# ESP_PIC_V2.net
KiCad netlist of a schematic drawn in Altium Designer
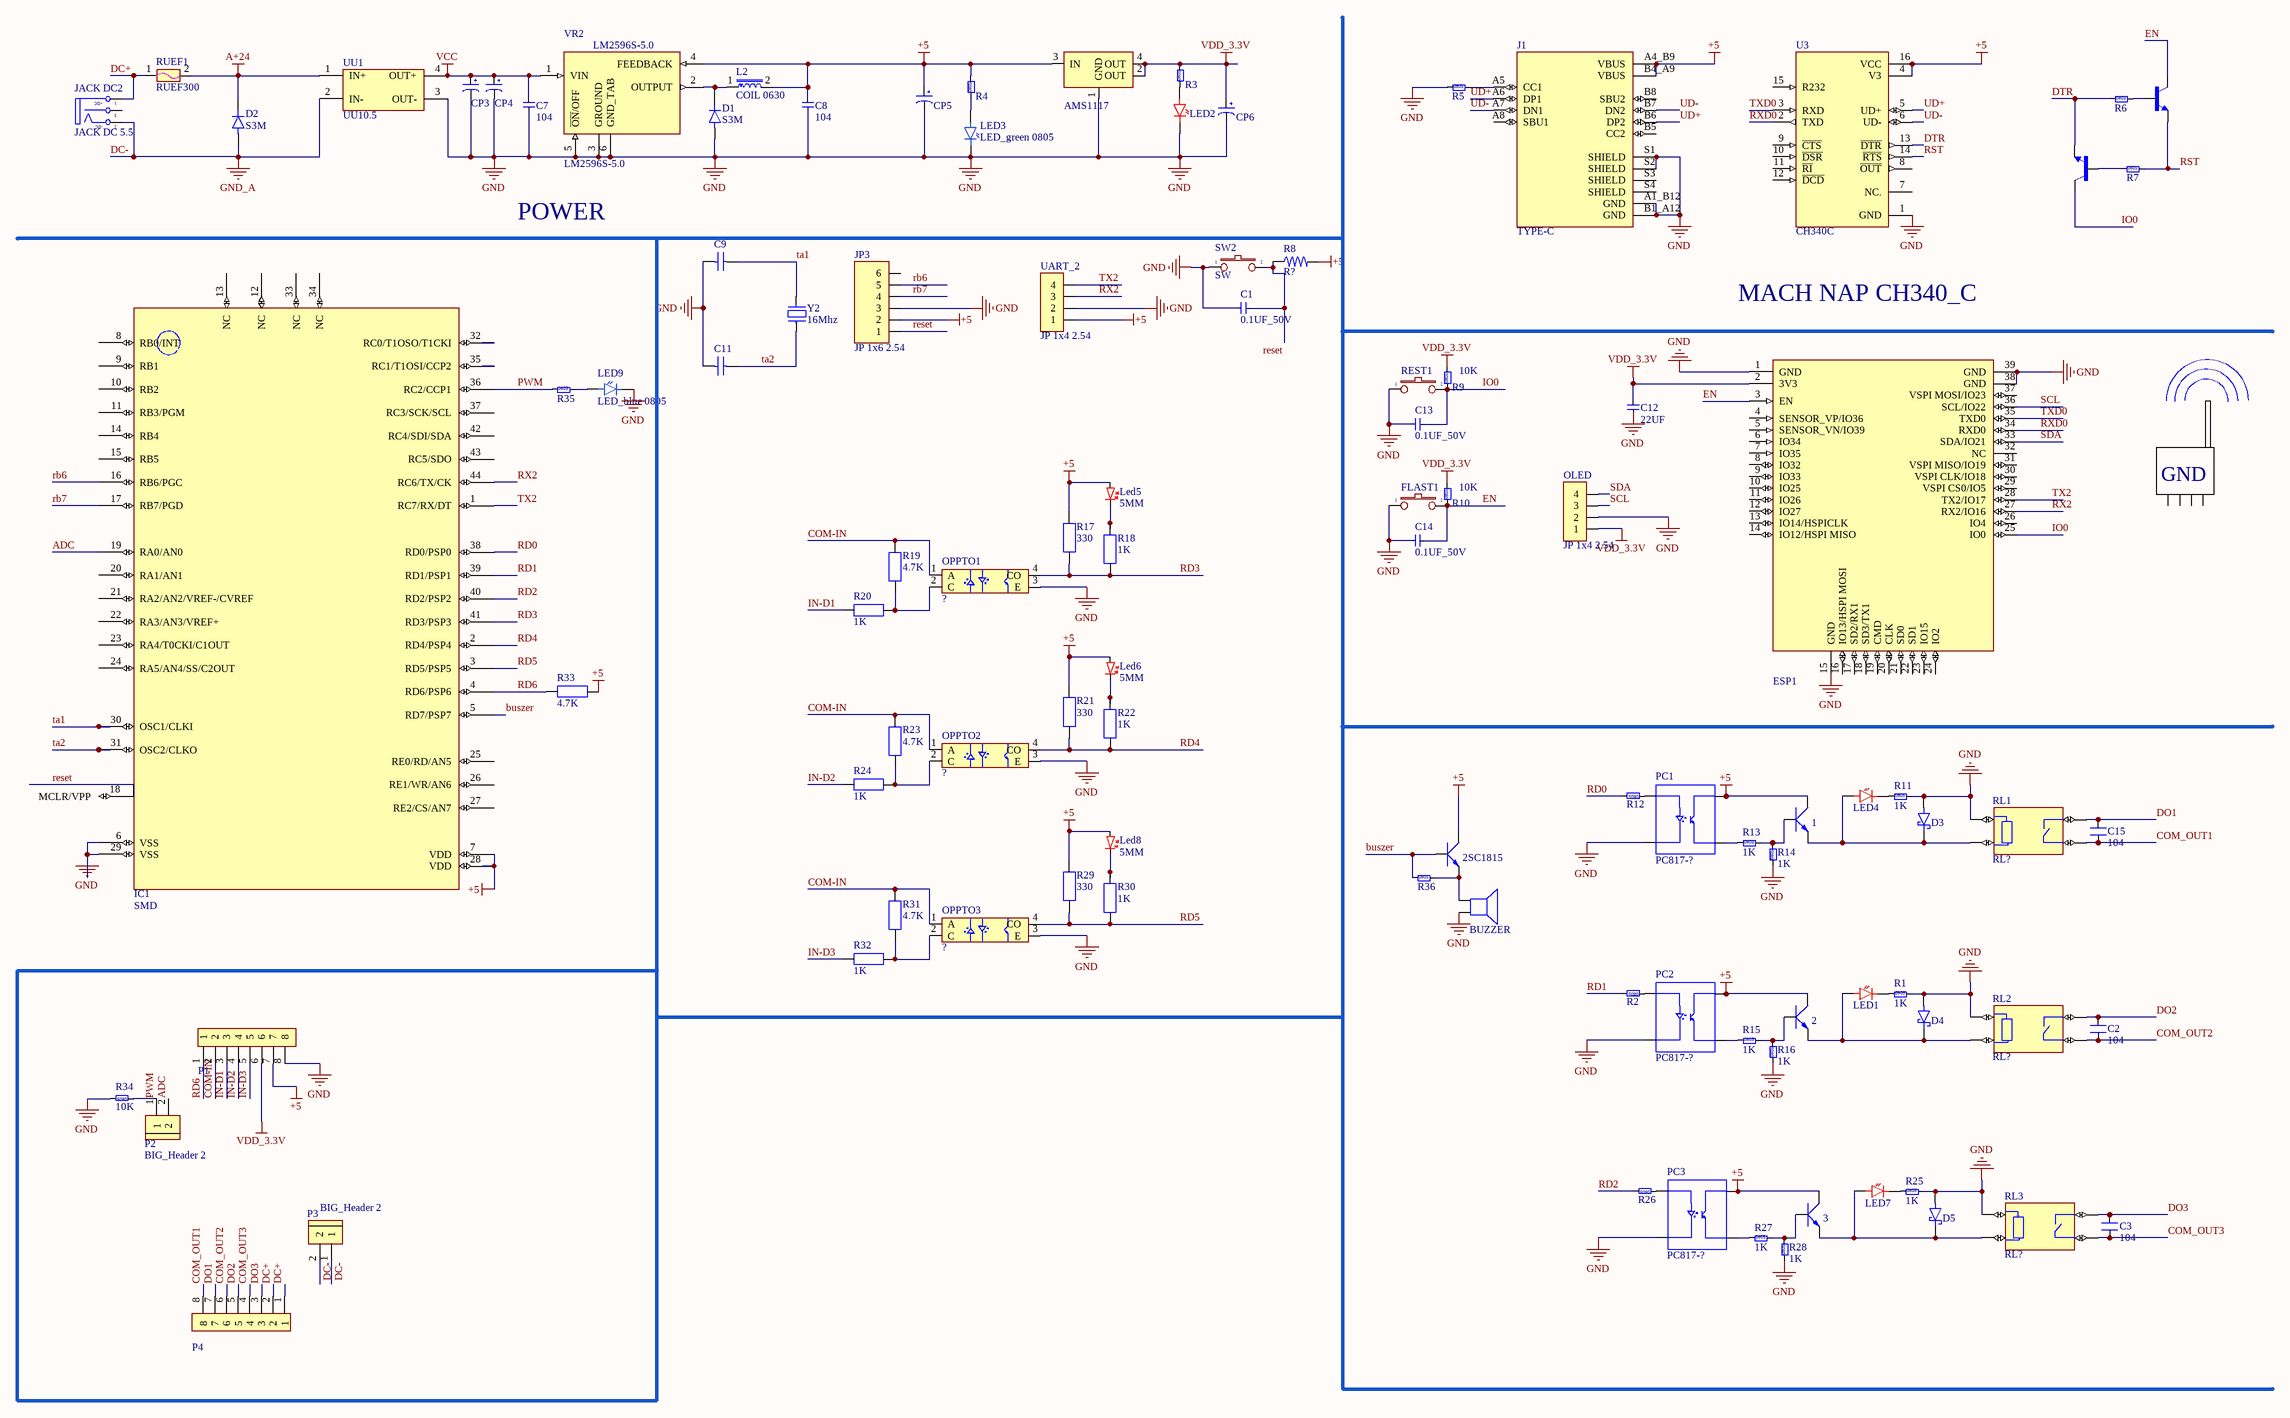
[diagram p0: ESP_PIC_V2.SchDoc]

(export (version "E")
  (design (tool "Eeschema 10.0.6"))
  (components
    (comp (ref "1")
      (value "2SC1815")
      (footprint "SOT23-3")
      (description "NPN-0.15A-50V")
      (libsource (lib "PLG_RC") (part "2SC1815-SMD"))
    )
    (comp (ref "2")
      (value "2SC1815")
      (footprint "SOT23-3")
      (description "NPN-0.15A-50V")
      (libsource (lib "PLG_RC") (part "2SC1815-SMD"))
    )
    (comp (ref "2SC1815")
      (value "2SC1815")
      (footprint "SOT23-3")
      (description "NPN-0.15A-50V")
      (libsource (lib "PLG_RC") (part "2SC1815-SMD"))
    )
    (comp (ref "3")
      (value "2SC1815")
      (footprint "SOT23-3")
      (description "NPN-0.15A-50V")
      (libsource (lib "PLG_RC") (part "2SC1815-SMD"))
    )
    (comp (ref "AMS1117")
      (value "AMS1117")
      (footprint "SOT223-4M_AMS1117_3V3")
      (description "800mA- 3.3V - SMD")
      (libsource (lib "PLG_RC") (part "AMS1117-3.3-SMD"))
    )
    (comp (ref "BUZZER")
      (value "BUZZER")
      (footprint "Coi Chip Speacker")
      (description "Còi chip")
      (libsource (lib "PLG_RC") (part "BUZZER"))
    )
    (comp (ref "C1")
      (value "0.1UF_50V")
      (footprint "CAP0805")
      (description "CAP 0805 KHÔNG PHÂN CỰC SMD")
      (fields
        (field (name "MANUFACTURER") "TDK Corporation")
        (field (name "MANUFACTURER PART NUMBER") "C3216JB1V226M160AC")
      )
      (libsource (lib "PLG_RC") (part "CAP 0805"))
    )
    (comp (ref "C2")
      (value "104")
      (footprint "CN2")
      (description "Cap np 104 => 105pF")
      (libsource (lib "TH_PHUOC") (part "CN2"))
    )
    (comp (ref "C3")
      (value "104")
      (footprint "CN2")
      (description "Cap np 104 => 105pF")
      (libsource (lib "TH_PHUOC") (part "CN2"))
    )
    (comp (ref "C7")
      (value "104")
      (footprint "CAP0805")
      (description "CAP 0805 KHÔNG PHÂN CỰC SMD")
      (fields
        (field (name "MANUFACTURER") "TDK Corporation")
        (field (name "MANUFACTURER PART NUMBER") "C3216JB1V226M160AC")
      )
      (libsource (lib "PLG_RC") (part "CAP 0805"))
    )
    (comp (ref "C8")
      (value "104")
      (footprint "CAP0805")
      (description "CAP 0805 KHÔNG PHÂN CỰC SMD")
      (fields
        (field (name "MANUFACTURER") "TDK Corporation")
        (field (name "MANUFACTURER PART NUMBER") "C3216JB1V226M160AC")
      )
      (libsource (lib "PLG_RC") (part "CAP 0805"))
    )
    (comp (ref "C9")
      (value "Capacitor Ceramic")
      (footprint "C0805")
      (description "Capacitor")
      (fields (field (name "PUBLISHER") "Altium Limited"))
      (libsource (lib "Cty1") (part "CapSMD"))
    )
    (comp (ref "C11")
      (value "Capacitor Ceramic")
      (footprint "C0805")
      (description "Capacitor")
      (fields (field (name "PUBLISHER") "Altium Limited"))
      (libsource (lib "Cty1") (part "CapSMD"))
    )
    (comp (ref "C12")
      (value "22UF")
      (footprint "CAP0805")
      (description "CAP 0805 KHÔNG PHÂN CỰC SMD")
      (fields
        (field (name "MANUFACTURER") "TDK Corporation")
        (field (name "MANUFACTURER PART NUMBER") "C3216JB1V226M160AC")
      )
      (libsource (lib "PLG_RC") (part "CAP 0805"))
    )
    (comp (ref "C13")
      (value "0.1UF_50V")
      (footprint "CAP0805")
      (description "CAP 0805 KHÔNG PHÂN CỰC SMD")
      (fields
        (field (name "MANUFACTURER") "TDK Corporation")
        (field (name "MANUFACTURER PART NUMBER") "C3216JB1V226M160AC")
      )
      (libsource (lib "PLG_RC") (part "CAP 0805"))
    )
    (comp (ref "C14")
      (value "0.1UF_50V")
      (footprint "CAP0805")
      (description "CAP 0805 KHÔNG PHÂN CỰC SMD")
      (fields
        (field (name "MANUFACTURER") "TDK Corporation")
        (field (name "MANUFACTURER PART NUMBER") "C3216JB1V226M160AC")
      )
      (libsource (lib "PLG_RC") (part "CAP 0805"))
    )
    (comp (ref "C15")
      (value "104")
      (footprint "CN2")
      (description "Cap np 104 => 105pF")
      (libsource (lib "TH_PHUOC") (part "CN2"))
    )
    (comp (ref "CP3")
      (value "CP?")
      (footprint "C10mm")
      (description "CP 1000UF/35V")
      (libsource (lib "PLG_RC") (part "CP 1000UF/35V"))
    )
    (comp (ref "CP4")
      (value "CP?")
      (footprint "C10mm")
      (description "CP 1000UF/35V")
      (libsource (lib "PLG_RC") (part "CP 1000UF/35V"))
    )
    (comp (ref "CP5")
      (value "220UF/16V")
      (footprint "CAP SMD ALUMINUM D8")
      (description "SMD")
      (libsource (lib "PLG_RC") (part "TỤ NHÔM 220UF 16V"))
    )
    (comp (ref "CP6")
      (value "220UF/16V")
      (footprint "CAP SMD ALUMINUM D8")
      (description "SMD")
      (libsource (lib "PLG_RC") (part "TỤ NHÔM 220UF 16V"))
    )
    (comp (ref "D1")
      (value "S3M")
      (footprint "S3M")
      (description "Diode Standard 1000 V 3A Surface Mount SMC (DO-214AB)")
      (fields (field (name "MF") "ON Semiconductor"))
      (libsource (lib "PLG_RC") (part "S3M"))
    )
    (comp (ref "D2")
      (value "S3M")
      (footprint "S3M")
      (description "Diode Standard 1000 V 3A Surface Mount SMC (DO-214AB)")
      (fields (field (name "MF") "ON Semiconductor"))
      (libsource (lib "PLG_RC") (part "S3M"))
    )
    (comp (ref "D3")
      (value "D?")
      (footprint "SS210")
      (description "2A, 100V, Schottky Rectifier")
      (fields (field (name "MF") "Taiwan Semiconductor") (field (name "MP") "SS210"))
      (libsource (lib "LeQuangDinh") (part "SS210"))
    )
    (comp (ref "D4")
      (value "D?")
      (footprint "SS210")
      (description "2A, 100V, Schottky Rectifier")
      (fields (field (name "MF") "Taiwan Semiconductor") (field (name "MP") "SS210"))
      (libsource (lib "LeQuangDinh") (part "SS210"))
    )
    (comp (ref "D5")
      (value "D?")
      (footprint "SS210")
      (description "2A, 100V, Schottky Rectifier")
      (fields (field (name "MF") "Taiwan Semiconductor") (field (name "MP") "SS210"))
      (libsource (lib "LeQuangDinh") (part "SS210"))
    )
    (comp (ref "ESP1") (value "ESP32-U") (footprint "ESP32-U") (libsource (lib "PLG_RC") (part "ESP32-U")))
    (comp (ref "FLAST1")
      (value "BUTTON?")
      (footprint "SW1-SMD")
      (description "button 2 pin")
      (libsource (lib "PLG_RC") (part "BUTTON"))
    )
    (comp (ref "IC1")
      (value "SMD")
      (footprint "TQFP_44pin")
      (description "IC SMD")
      (libsource (lib "MIHPHONG_lib") (part "16F877A SMD"))
    )
    (comp (ref "IPEX")
      (value "IPEX")
      (footprint "DE ANTEN ESP")
      (libsource (lib "PLG_RC") (part "ANTEN_IPEX_SMA"))
    )
    (comp (ref "J1")
      (value "TYPE-C")
      (footprint "USB-TYPE-C")
      (description "USB Connectors 24 Receptacle 1 8.94*7.3mm RoHS")
      (fields (field (name "MF") "HRO Electronics Co., Ltd.") (field (name "MP") "TYPE-C-31-M-12"))
      (libsource (lib "PLG_RC") (part "TYPE-C"))
    )
    (comp (ref "JACK DC2")
      (value "JACK DC 5.5")
      (footprint "JACK DC 5.5")
      (libsource (lib "PLG_RC") (part "JACK DC 5.5"))
    )
    (comp (ref "JP3")
      (value "JP 1x6 2.54")
      (footprint "JP 1x6 DT")
      (description "Cắm")
      (libsource (lib "LeQuangDinh1") (part "JP 1x6 2.54 Duc Thang"))
    )
    (comp (ref "L2")
      (value "COIL 0630")
      (footprint "COIL 0630")
      (description "SMD Inductor 10uH-20%-5A")
      (fields (field (name "MP") "CSAB0630-100M") (field (name "MF") "Codaca"))
      (libsource (lib "PLG_RC") (part "COIL 0630"))
    )
    (comp (ref "LED1")
      (value "LED?")
      (footprint "LED_SMD0805_RED - duplicate")
      (description "SMD 0805")
      (libsource (lib "LeQuangDinh") (part "LED SMD 0805"))
    )
    (comp (ref "LED2")
      (value "LED?")
      (footprint "LEDBLUE 0805")
      (description "SMD 0805")
      (libsource (lib "PLG_RC") (part "LED SMD"))
    )
    (comp (ref "LED3")
      (value "LED_green 0805")
      (footprint "LEDgreen 0805")
      (libsource (lib "PLG_RC") (part "LED_green 0805"))
    )
    (comp (ref "LED4")
      (value "LED?")
      (footprint "LED_SMD0805_RED - duplicate")
      (description "SMD 0805")
      (libsource (lib "LeQuangDinh") (part "LED SMD 0805"))
    )
    (comp (ref "Led5")
      (value "5MM")
      (footprint "LEDGREEN 0805")
      (libsource (lib "lequandinh tinker") (part "LED RED 5MM"))
    )
    (comp (ref "Led6")
      (value "5MM")
      (footprint "LEDGREEN 0805")
      (libsource (lib "lequandinh tinker") (part "LED RED 5MM"))
    )
    (comp (ref "LED7")
      (value "LED?")
      (footprint "LED_SMD0805_RED - duplicate")
      (description "SMD 0805")
      (libsource (lib "LeQuangDinh") (part "LED SMD 0805"))
    )
    (comp (ref "Led8")
      (value "5MM")
      (footprint "LEDGREEN 0805")
      (libsource (lib "lequandinh tinker") (part "LED RED 5MM"))
    )
    (comp (ref "LED9")
      (value "LED_blue 0805")
      (footprint "LEDblue 0805")
      (libsource (lib "PLG_RC") (part "LED_blue 0805"))
    )
    (comp (ref "OLED")
      (value "JP 1x4 2.54")
      (footprint "JP 1x4 DT")
      (description "Cắm")
      (libsource (lib "PLG_RC") (part "JP 1x4 2.54 Duc Thang"))
    )
    (comp (ref "OPPTO1")
      (value "?")
      (footprint "OPTO_4-SMD")
      (description "SMD")
      (libsource (lib "lequandinh tinker") (part "OPTO 2C"))
    )
    (comp (ref "OPPTO2")
      (value "?")
      (footprint "OPTO_4-SMD")
      (description "SMD")
      (libsource (lib "lequandinh tinker") (part "OPTO 2C"))
    )
    (comp (ref "OPPTO3")
      (value "?")
      (footprint "OPTO_4-SMD")
      (description "SMD")
      (libsource (lib "lequandinh tinker") (part "OPTO 2C"))
    )
    (comp (ref "P1")
      (value "BIG Heager 8")
      (footprint "BIG_Header 8")
      (libsource (lib "TH_PHUOC") (part "BIG_Header 8"))
    )
    (comp (ref "P2")
      (value "BIG_Header 2")
      (footprint "BIG_Header 2")
      (libsource (lib "") (part "BIG_Header 2_1"))
    )
    (comp (ref "P3")
      (value "BIG_Header 2")
      (footprint "BIG_Header 2")
      (libsource (lib "TH_PHUOC") (part "BIG_Header 2"))
    )
    (comp (ref "P4")
      (value "BIG Heager 8")
      (footprint "BIG_Header 8")
      (libsource (lib "") (part "BIG_Header 8_1"))
    )
    (comp (ref "PC1")
      (value "PC817-?")
      (footprint "OPTO_4-SMD")
      (description "SMD")
      (libsource (lib "PLG_RC") (part "PC817 SMD"))
    )
    (comp (ref "PC2")
      (value "PC817-?")
      (footprint "OPTO_4-SMD")
      (description "SMD")
      (libsource (lib "PLG_RC") (part "PC817 SMD"))
    )
    (comp (ref "PC3")
      (value "PC817-?")
      (footprint "OPTO_4-SMD")
      (description "SMD")
      (libsource (lib "PLG_RC") (part "PC817 SMD"))
    )
    (comp (ref "Q1")
      (value "S8050-G")
      (footprint "SOT23-3")
      (description "Bipolar (BJT) Transistor NPN 25 V 1.5 A 100MHz 300 mW Surface Mount SOT-23-3")
      (fields (field (name "DIGI-KEY_PART_NUMBER") "641-1790-2-ND") (field (name "MP") "SS8050G"))
      (libsource (lib "PLG_RC") (part "S8050-G"))
    )
    (comp (ref "Q2")
      (value "S8050-G")
      (footprint "SOT23-3")
      (description "Bipolar (BJT) Transistor NPN 25 V 1.5 A 100MHz 300 mW Surface Mount SOT-23-3")
      (fields (field (name "DIGI-KEY_PART_NUMBER") "641-1790-2-ND") (field (name "MP") "SS8050G"))
      (libsource (lib "") (part "S8050-G_1"))
    )
    (comp (ref "R1")
      (value "1K")
      (footprint "RES 0805")
      (description "RES 0.36 OHM 1% 1/4W 0805")
      (fields (field (name "MF") "TE Connectivity") (field (name "MP") "2-2176053-1"))
      (libsource (lib "LeQuangDinh") (part "RES 0805 SMD"))
    )
    (comp (ref "R2")
      (value "RES 0805")
      (footprint "RES 0805")
      (description "RES 0.36 OHM 1% 1/4W 0805")
      (fields (field (name "MF") "TE Connectivity") (field (name "MP") "2-2176053-1"))
      (libsource (lib "PLG_RC") (part "RES 0805 SMD"))
    )
    (comp (ref "R3")
      (value "RES 0805")
      (footprint "RES 0805")
      (description "RES 0.36 OHM 1% 1/4W 0805")
      (fields (field (name "MF") "TE Connectivity") (field (name "MP") "2-2176053-1"))
      (libsource (lib "PLG_RC") (part "RES 0805 SMD"))
    )
    (comp (ref "R4")
      (value "RES 0805")
      (footprint "RES 0805")
      (description "RES 0.36 OHM 1% 1/4W 0805")
      (fields (field (name "MF") "TE Connectivity") (field (name "MP") "2-2176053-1"))
      (libsource (lib "PLG_RC") (part "RES 0805 SMD"))
    )
    (comp (ref "R5")
      (value "RES 0805")
      (footprint "RES 0805")
      (description "RES 0.36 OHM 1% 1/4W 0805")
      (fields (field (name "MF") "TE Connectivity") (field (name "MP") "2-2176053-1"))
      (libsource (lib "PLG_RC") (part "RES 0805 SMD"))
    )
    (comp (ref "R6")
      (value "RES 0805")
      (footprint "RES 0805")
      (description "RES 0.36 OHM 1% 1/4W 0805")
      (fields (field (name "MF") "TE Connectivity") (field (name "MP") "2-2176053-1"))
      (libsource (lib "PLG_RC") (part "RES 0805 SMD"))
    )
    (comp (ref "R7")
      (value "RES 0805")
      (footprint "RES 0805")
      (description "RES 0.36 OHM 1% 1/4W 0805")
      (fields (field (name "MF") "TE Connectivity") (field (name "MP") "2-2176053-1"))
      (libsource (lib "PLG_RC") (part "RES 0805 SMD"))
    )
    (comp (ref "R8")
      (value "R?")
      (footprint "RES 0805")
      (description "RES 0.36 OHM 1% 1/4W 0805")
      (fields (field (name "MF") "TE Connectivity") (field (name "MP") "2-2176053-1"))
      (libsource (lib "LeQuangDinh1") (part "RES 0805 SMD"))
    )
    (comp (ref "R9")
      (value "10K")
      (footprint "RES 0805")
      (description "RES 0.36 OHM 1% 1/4W 0805")
      (fields (field (name "MF") "TE Connectivity") (field (name "MP") "2-2176053-1"))
      (libsource (lib "PLG_RC") (part "RES 0805 SMD"))
    )
    (comp (ref "R10")
      (value "10K")
      (footprint "RES 0805")
      (description "RES 0.36 OHM 1% 1/4W 0805")
      (fields (field (name "MF") "TE Connectivity") (field (name "MP") "2-2176053-1"))
      (libsource (lib "PLG_RC") (part "RES 0805 SMD"))
    )
    (comp (ref "R11")
      (value "1K")
      (footprint "RES 0805")
      (description "RES 0.36 OHM 1% 1/4W 0805")
      (fields (field (name "MF") "TE Connectivity") (field (name "MP") "2-2176053-1"))
      (libsource (lib "LeQuangDinh") (part "RES 0805 SMD"))
    )
    (comp (ref "R12")
      (value "RES 0805")
      (footprint "RES 0805")
      (description "RES 0.36 OHM 1% 1/4W 0805")
      (fields (field (name "MF") "TE Connectivity") (field (name "MP") "2-2176053-1"))
      (libsource (lib "PLG_RC") (part "RES 0805 SMD"))
    )
    (comp (ref "R13")
      (value "1K")
      (footprint "RES 0805")
      (description "RES 0.36 OHM 1% 1/4W 0805")
      (fields (field (name "MF") "TE Connectivity") (field (name "MP") "2-2176053-1"))
      (libsource (lib "LeQuangDinh") (part "RES 0805 SMD"))
    )
    (comp (ref "R14")
      (value "1K")
      (footprint "RES 0805")
      (description "RES 0.36 OHM 1% 1/4W 0805")
      (fields (field (name "MF") "TE Connectivity") (field (name "MP") "2-2176053-1"))
      (libsource (lib "LeQuangDinh") (part "RES 0805 SMD"))
    )
    (comp (ref "R15")
      (value "1K")
      (footprint "RES 0805")
      (description "RES 0.36 OHM 1% 1/4W 0805")
      (fields (field (name "MF") "TE Connectivity") (field (name "MP") "2-2176053-1"))
      (libsource (lib "LeQuangDinh") (part "RES 0805 SMD"))
    )
    (comp (ref "R16")
      (value "1K")
      (footprint "RES 0805")
      (description "RES 0.36 OHM 1% 1/4W 0805")
      (fields (field (name "MF") "TE Connectivity") (field (name "MP") "2-2176053-1"))
      (libsource (lib "LeQuangDinh") (part "RES 0805 SMD"))
    )
    (comp (ref "R17")
      (value "330")
      (footprint "RES 0805")
      (description "DIP")
      (libsource (lib "lequandinh tinker") (part "RESISTOR  1/4W 4.7K"))
    )
    (comp (ref "R18")
      (value "1K")
      (footprint "RES 0805")
      (description "DIP")
      (libsource (lib "lequandinh tinker") (part "RESISTOR  1/4W 1K"))
    )
    (comp (ref "R19")
      (value "4.7K")
      (footprint "RES 0805")
      (description "DIP")
      (libsource (lib "lequandinh tinker") (part "RESISTOR  1/4W 4.7K"))
    )
    (comp (ref "R20")
      (value "1K")
      (footprint "RES 0805")
      (description "DIP")
      (libsource (lib "lequandinh tinker") (part "RESISTOR  1/4W 1K"))
    )
    (comp (ref "R21")
      (value "330")
      (footprint "RES 0805")
      (description "DIP")
      (libsource (lib "lequandinh tinker") (part "RESISTOR  1/4W 4.7K"))
    )
    (comp (ref "R22")
      (value "1K")
      (footprint "RES 0805")
      (description "DIP")
      (libsource (lib "lequandinh tinker") (part "RESISTOR  1/4W 1K"))
    )
    (comp (ref "R23")
      (value "4.7K")
      (footprint "RES 0805")
      (description "DIP")
      (libsource (lib "lequandinh tinker") (part "RESISTOR  1/4W 4.7K"))
    )
    (comp (ref "R24")
      (value "1K")
      (footprint "RES 0805")
      (description "DIP")
      (libsource (lib "lequandinh tinker") (part "RESISTOR  1/4W 1K"))
    )
    (comp (ref "R25")
      (value "1K")
      (footprint "RES 0805")
      (description "RES 0.36 OHM 1% 1/4W 0805")
      (fields (field (name "MF") "TE Connectivity") (field (name "MP") "2-2176053-1"))
      (libsource (lib "LeQuangDinh") (part "RES 0805 SMD"))
    )
    (comp (ref "R26")
      (value "RES 0805")
      (footprint "RES 0805")
      (description "RES 0.36 OHM 1% 1/4W 0805")
      (fields (field (name "MF") "TE Connectivity") (field (name "MP") "2-2176053-1"))
      (libsource (lib "PLG_RC") (part "RES 0805 SMD"))
    )
    (comp (ref "R27")
      (value "1K")
      (footprint "RES 0805")
      (description "RES 0.36 OHM 1% 1/4W 0805")
      (fields (field (name "MF") "TE Connectivity") (field (name "MP") "2-2176053-1"))
      (libsource (lib "LeQuangDinh") (part "RES 0805 SMD"))
    )
    (comp (ref "R28")
      (value "1K")
      (footprint "RES 0805")
      (description "RES 0.36 OHM 1% 1/4W 0805")
      (fields (field (name "MF") "TE Connectivity") (field (name "MP") "2-2176053-1"))
      (libsource (lib "LeQuangDinh") (part "RES 0805 SMD"))
    )
    (comp (ref "R29")
      (value "330")
      (footprint "RES 0805")
      (description "DIP")
      (libsource (lib "lequandinh tinker") (part "RESISTOR  1/4W 4.7K"))
    )
    (comp (ref "R30")
      (value "1K")
      (footprint "RES 0805")
      (description "DIP")
      (libsource (lib "lequandinh tinker") (part "RESISTOR  1/4W 1K"))
    )
    (comp (ref "R31")
      (value "4.7K")
      (footprint "RES 0805")
      (description "DIP")
      (libsource (lib "lequandinh tinker") (part "RESISTOR  1/4W 4.7K"))
    )
    (comp (ref "R32")
      (value "1K")
      (footprint "RES 0805")
      (description "DIP")
      (libsource (lib "lequandinh tinker") (part "RESISTOR  1/4W 1K"))
    )
    (comp (ref "R33")
      (value "4.7K")
      (footprint "RES 0805")
      (description "DIP")
      (libsource (lib "lequandinh tinker") (part "RESISTOR  1/4W 4.7K"))
    )
    (comp (ref "R34")
      (value "10K")
      (footprint "RES 0805")
      (description "RES 0.36 OHM 1% 1/4W 0805")
      (fields (field (name "MF") "TE Connectivity") (field (name "MP") "2-2176053-1"))
      (libsource (lib "PLG_RC") (part "RES 0805 SMD"))
    )
    (comp (ref "R35")
      (value "RES 0805")
      (footprint "RES 0805")
      (description "RES 0.36 OHM 1% 1/4W 0805")
      (fields (field (name "MF") "TE Connectivity") (field (name "MP") "2-2176053-1"))
      (libsource (lib "PLG_RC") (part "RES 0805 SMD"))
    )
    (comp (ref "R36")
      (value "RES 0805")
      (footprint "RES 0805")
      (description "RES 0.36 OHM 1% 1/4W 0805")
      (fields (field (name "MF") "TE Connectivity") (field (name "MP") "2-2176053-1"))
      (libsource (lib "PLG_RC") (part "RES 0805 SMD"))
    )
    (comp (ref "REST1")
      (value "BUTTON?")
      (footprint "SW1-SMD")
      (description "button 2 pin")
      (libsource (lib "PLG_RC") (part "BUTTON"))
    )
    (comp (ref "RL1")
      (value "RL?")
      (footprint "HF46F/005-HS1")
      (description "Relay: electromagnetic; SPST-NO; Ucoil: 5VDC; 5A/250VAC; 5A/30VDC")
      (fields (field (name "MP") "HF46F/005-HS1") (field (name "MF") "Hongfa"))
      (libsource (lib "LeQuangDinh") (part "HK46F"))
    )
    (comp (ref "RL2")
      (value "RL?")
      (footprint "HF46F/005-HS1")
      (description "Relay: electromagnetic; SPST-NO; Ucoil: 5VDC; 5A/250VAC; 5A/30VDC")
      (fields (field (name "MP") "HF46F/005-HS1") (field (name "MF") "Hongfa"))
      (libsource (lib "LeQuangDinh") (part "HK46F"))
    )
    (comp (ref "RL3")
      (value "RL?")
      (footprint "HF46F/005-HS1")
      (description "Relay: electromagnetic; SPST-NO; Ucoil: 5VDC; 5A/250VAC; 5A/30VDC")
      (fields (field (name "MP") "HF46F/005-HS1") (field (name "MF") "Hongfa"))
      (libsource (lib "LeQuangDinh") (part "HK46F"))
    )
    (comp (ref "RUEF1") (value "RUEF300") (footprint "RUEF300") (libsource (lib "PLG_RC") (part "RUEF300")))
    (comp (ref "SW2")
      (value "SW")
      (footprint "SW1-SMD")
      (description "Switch button 2 pin")
      (libsource (lib "LeQuangDinh1") (part "SW2"))
    )
    (comp (ref "U3")
      (value "CH340C")
      (footprint "SOIC127P600X180-16N")
      (description "USB to serial chip CH340")
      (fields (field (name "MF") "WCH"))
      (libsource (lib "PLG_RC") (part "CH340C"))
    )
    (comp (ref "UART_2")
      (value "JP 1x4 2.54")
      (footprint "JP 1x4 DT")
      (description "Cắm")
      (libsource (lib "PLG_RC") (part "JP 1x4 2.54 Duc Thang"))
    )
    (comp (ref "UU1")
      (value "UU10.5")
      (footprint "UU10.5")
      (libsource (lib "lequandinh tinker") (part "UU10.5 10X13"))
    )
    (comp (ref "VR2")
      (value "LM2596S-5.0")
      (footprint "TO 263 - 5")
      (description "SIMPLE SWITCHER&reg; 4.5V to 40V, 3A Low Component Count Step-Down Regulator")
      (fields (field (name "MP") "LM2596S-5.0/NOPB") (field (name "MF") "Texas Instruments"))
      (libsource (lib "PLG_RC") (part "LM2596S-5.0"))
    )
    (comp (ref "Y2")
      (value "16Mhz")
      (footprint "Thach Anh 2 chan cam")
      (description "Crystal For all Crystal 2pin.")
      (libsource (lib "LeQuangDinh1") (part "Thach Anh 2 chan Cam"))
    )
  )
  (nets
    (net (code "1") (name "+5") (class "Default")
      (node (ref "1") (pin "2") (pinfunction "C_2") (pintype "passive"))
      (node (ref "2") (pin "2") (pinfunction "C_2") (pintype "passive"))
      (node (ref "2SC1815") (pin "2") (pinfunction "C_2") (pintype "passive"))
      (node (ref "3") (pin "2") (pinfunction "C_2") (pintype "passive"))
      (node (ref "AMS1117") (pin "3") (pinfunction "IN_3") (pintype "passive"))
      (node (ref "C8") (pin "1") (pinfunction "1_1") (pintype "passive"))
      (node (ref "CP5") (pin "1") (pinfunction "1_1") (pintype "passive"))
      (node (ref "IC1") (pin "28") (pinfunction "VDD_28") (pintype "bidirectional"))
      (node (ref "IC1") (pin "7") (pinfunction "VDD_7") (pintype "bidirectional"))
      (node (ref "J1") (pin "A4_B9") (pinfunction "VBUS_A4_B9") (pintype "power_in"))
      (node (ref "J1") (pin "B4_A9") (pinfunction "VBUS_B4_A9") (pintype "power_in"))
      (node (ref "JP3") (pin "2") (pinfunction "2_2") (pintype "passive"))
      (node (ref "L2") (pin "2") (pinfunction "2_2") (pintype "passive"))
      (node (ref "Led5") (pin "1") (pinfunction "B_1") (pintype "passive"))
      (node (ref "Led6") (pin "1") (pinfunction "B_1") (pintype "passive"))
      (node (ref "Led8") (pin "1") (pinfunction "B_1") (pintype "passive"))
      (node (ref "P1") (pin "7") (pinfunction "7_7") (pintype "passive"))
      (node (ref "PC1") (pin "4") (pinfunction "CO_4") (pintype "passive"))
      (node (ref "PC2") (pin "4") (pinfunction "CO_4") (pintype "passive"))
      (node (ref "PC3") (pin "4") (pinfunction "CO_4") (pintype "passive"))
      (node (ref "R17") (pin "1") (pinfunction "1_1") (pintype "passive"))
      (node (ref "R21") (pin "1") (pinfunction "1_1") (pintype "passive"))
      (node (ref "R29") (pin "1") (pinfunction "1_1") (pintype "passive"))
      (node (ref "R33") (pin "2") (pinfunction "2_2") (pintype "passive"))
      (node (ref "R4") (pin "2") (pinfunction "2_2") (pintype "passive"))
      (node (ref "R8") (pin "2") (pinfunction "2_2") (pintype "passive"))
      (node (ref "U3") (pin "16") (pinfunction "VCC_16") (pintype "power_in"))
      (node (ref "U3") (pin "4") (pinfunction "V3_4") (pintype "power_in"))
      (node (ref "UART_2") (pin "1") (pinfunction "1_1") (pintype "passive"))
      (node (ref "VR2") (pin "4") (pinfunction "FEEDBACK_4") (pintype "input"))
    )
    (net (code "2") (name "/ADC") (class "Default")
      (node (ref "IC1") (pin "19") (pinfunction "RA0/AN0_19") (pintype "bidirectional"))
      (node (ref "P2") (pin "2") (pinfunction "2_2") (pintype "passive"))
    )
    (net (code "3") (name "/COM-IN") (class "Default")
      (node (ref "OPPTO1") (pin "1") (pinfunction "A_1") (pintype "passive"))
      (node (ref "OPPTO2") (pin "1") (pinfunction "A_1") (pintype "passive"))
      (node (ref "OPPTO3") (pin "1") (pinfunction "A_1") (pintype "passive"))
      (node (ref "P1") (pin "2") (pinfunction "2_2") (pintype "passive"))
      (node (ref "R19") (pin "1") (pinfunction "1_1") (pintype "passive"))
      (node (ref "R23") (pin "1") (pinfunction "1_1") (pintype "passive"))
      (node (ref "R31") (pin "1") (pinfunction "1_1") (pintype "passive"))
    )
    (net (code "4") (name "/COM_OUT1") (class "Default")
      (node (ref "C15") (pin "1") (pinfunction "1_1") (pintype "passive"))
      (node (ref "P4") (pin "8") (pinfunction "8_8") (pintype "passive"))
      (node (ref "RL1") (pin "3") (pinfunction "3_3") (pintype "bidirectional"))
    )
    (net (code "5") (name "/COM_OUT2") (class "Default")
      (node (ref "C2") (pin "1") (pinfunction "1_1") (pintype "passive"))
      (node (ref "P4") (pin "6") (pinfunction "6_6") (pintype "passive"))
      (node (ref "RL2") (pin "3") (pinfunction "3_3") (pintype "bidirectional"))
    )
    (net (code "6") (name "/COM_OUT3") (class "Default")
      (node (ref "C3") (pin "1") (pinfunction "1_1") (pintype "passive"))
      (node (ref "P4") (pin "4") (pinfunction "4_4") (pintype "passive"))
      (node (ref "RL3") (pin "3") (pinfunction "3_3") (pintype "bidirectional"))
    )
    (net (code "7") (name "/DC+") (class "Default")
      (node (ref "JACK DC2") (pin "1") (pinfunction "T_1") (pintype "passive"))
      (node (ref "P4") (pin "1") (pinfunction "1_1") (pintype "passive"))
      (node (ref "P4") (pin "2") (pinfunction "2_2") (pintype "passive"))
      (node (ref "RUEF1") (pin "1") (pinfunction "1_1") (pintype "passive"))
    )
    (net (code "8") (name "/DO1") (class "Default")
      (node (ref "C15") (pin "2") (pinfunction "2_2") (pintype "passive"))
      (node (ref "P4") (pin "7") (pinfunction "7_7") (pintype "passive"))
      (node (ref "RL1") (pin "4") (pinfunction "4_4") (pintype "bidirectional"))
    )
    (net (code "9") (name "/DO2") (class "Default")
      (node (ref "C2") (pin "2") (pinfunction "2_2") (pintype "passive"))
      (node (ref "P4") (pin "5") (pinfunction "5_5") (pintype "passive"))
      (node (ref "RL2") (pin "4") (pinfunction "4_4") (pintype "bidirectional"))
    )
    (net (code "10") (name "/DO3") (class "Default")
      (node (ref "C3") (pin "2") (pinfunction "2_2") (pintype "passive"))
      (node (ref "P4") (pin "3") (pinfunction "3_3") (pintype "passive"))
      (node (ref "RL3") (pin "4") (pinfunction "4_4") (pintype "bidirectional"))
    )
    (net (code "11") (name "/DTR") (class "Default")
      (node (ref "Q2") (pin "2") (pinfunction "E_2") (pintype "passive"))
      (node (ref "R6") (pin "1") (pinfunction "1_1") (pintype "passive"))
      (node (ref "U3") (pin "13") (pinfunction "~{DTR}_13") (pintype "output"))
    )
    (net (code "12") (name "/EN") (class "Default")
      (node (ref "C14") (pin "2") (pinfunction "2_2") (pintype "passive"))
      (node (ref "ESP1") (pin "3") (pinfunction "EN_3") (pintype "input"))
      (node (ref "FLAST1") (pin "2") (pinfunction "2_2") (pintype "passive"))
      (node (ref "Q1") (pin "3") (pinfunction "C_3") (pintype "passive"))
      (node (ref "R10") (pin "1") (pinfunction "1_1") (pintype "passive"))
    )
    (net (code "13") (name "/IN-D1") (class "Default")
      (node (ref "P1") (pin "3") (pinfunction "3_3") (pintype "passive"))
      (node (ref "R20") (pin "1") (pinfunction "1_1") (pintype "passive"))
    )
    (net (code "14") (name "/IN-D2") (class "Default")
      (node (ref "P1") (pin "4") (pinfunction "4_4") (pintype "passive"))
      (node (ref "R24") (pin "1") (pinfunction "1_1") (pintype "passive"))
    )
    (net (code "15") (name "/IN-D3") (class "Default")
      (node (ref "P1") (pin "5") (pinfunction "5_5") (pintype "passive"))
      (node (ref "R32") (pin "1") (pinfunction "1_1") (pintype "passive"))
    )
    (net (code "16") (name "/IO0") (class "Default")
      (node (ref "C13") (pin "2") (pinfunction "2_2") (pintype "passive"))
      (node (ref "ESP1") (pin "25") (pinfunction "IO0_25") (pintype "bidirectional"))
      (node (ref "Q2") (pin "3") (pinfunction "C_3") (pintype "passive"))
      (node (ref "R9") (pin "1") (pinfunction "1_1") (pintype "passive"))
      (node (ref "REST1") (pin "2") (pinfunction "2_2") (pintype "passive"))
    )
    (net (code "17") (name "/PWM") (class "Default")
      (node (ref "IC1") (pin "36") (pinfunction "RC2/CCP1_36") (pintype "bidirectional"))
      (node (ref "P2") (pin "1") (pinfunction "1_1") (pintype "passive"))
      (node (ref "R34") (pin "1") (pinfunction "1_1") (pintype "passive"))
      (node (ref "R35") (pin "1") (pinfunction "1_1") (pintype "passive"))
    )
    (net (code "18") (name "/RD0") (class "Default")
      (node (ref "IC1") (pin "38") (pinfunction "RD0/PSP0_38") (pintype "bidirectional"))
      (node (ref "R12") (pin "2") (pinfunction "2_2") (pintype "passive"))
    )
    (net (code "19") (name "/RD1") (class "Default")
      (node (ref "IC1") (pin "39") (pinfunction "RD1/PSP1_39") (pintype "bidirectional"))
      (node (ref "R2") (pin "2") (pinfunction "2_2") (pintype "passive"))
    )
    (net (code "20") (name "/RD2") (class "Default")
      (node (ref "IC1") (pin "40") (pinfunction "RD2/PSP2_40") (pintype "bidirectional"))
      (node (ref "R26") (pin "2") (pinfunction "2_2") (pintype "passive"))
    )
    (net (code "21") (name "/RD3") (class "Default")
      (node (ref "IC1") (pin "41") (pinfunction "RD3/PSP3_41") (pintype "bidirectional"))
      (node (ref "OPPTO1") (pin "4") (pinfunction "CO_4") (pintype "passive"))
      (node (ref "R17") (pin "2") (pinfunction "2_2") (pintype "passive"))
      (node (ref "R18") (pin "2") (pinfunction "2_2") (pintype "passive"))
    )
    (net (code "22") (name "/RD4") (class "Default")
      (node (ref "IC1") (pin "2") (pinfunction "RD4/PSP4_2") (pintype "bidirectional"))
      (node (ref "OPPTO2") (pin "4") (pinfunction "CO_4") (pintype "passive"))
      (node (ref "R21") (pin "2") (pinfunction "2_2") (pintype "passive"))
      (node (ref "R22") (pin "2") (pinfunction "2_2") (pintype "passive"))
    )
    (net (code "23") (name "/RD5") (class "Default")
      (node (ref "IC1") (pin "3") (pinfunction "RD5/PSP5_3") (pintype "bidirectional"))
      (node (ref "OPPTO3") (pin "4") (pinfunction "CO_4") (pintype "passive"))
      (node (ref "R29") (pin "2") (pinfunction "2_2") (pintype "passive"))
      (node (ref "R30") (pin "2") (pinfunction "2_2") (pintype "passive"))
    )
    (net (code "24") (name "/RD6") (class "Default")
      (node (ref "IC1") (pin "4") (pinfunction "RD6/PSP6_4") (pintype "bidirectional"))
      (node (ref "P1") (pin "1") (pinfunction "1_1") (pintype "passive"))
      (node (ref "R33") (pin "1") (pinfunction "1_1") (pintype "passive"))
    )
    (net (code "25") (name "/RST") (class "Default")
      (node (ref "Q1") (pin "2") (pinfunction "E_2") (pintype "passive"))
      (node (ref "R7") (pin "2") (pinfunction "2_2") (pintype "passive"))
      (node (ref "U3") (pin "14") (pinfunction "~{RTS}_14") (pintype "output"))
    )
    (net (code "26") (name "/RX2") (class "Default")
      (node (ref "ESP1") (pin "27") (pinfunction "RX2/IO16_27") (pintype "bidirectional"))
      (node (ref "IC1") (pin "44") (pinfunction "RC6/TX/CK_44") (pintype "bidirectional"))
      (node (ref "UART_2") (pin "3") (pinfunction "3_3") (pintype "passive"))
    )
    (net (code "27") (name "/RXD0") (class "Default")
      (node (ref "ESP1") (pin "34") (pinfunction "RXD0_34") (pintype "bidirectional"))
      (node (ref "U3") (pin "2") (pinfunction "TXD_2") (pintype "output"))
    )
    (net (code "28") (name "/SCL") (class "Default")
      (node (ref "ESP1") (pin "36") (pinfunction "SCL/IO22_36") (pintype "bidirectional"))
      (node (ref "OLED") (pin "3") (pinfunction "3_3") (pintype "passive"))
    )
    (net (code "29") (name "/SDA") (class "Default")
      (node (ref "ESP1") (pin "33") (pinfunction "SDA/IO21_33") (pintype "bidirectional"))
      (node (ref "OLED") (pin "4") (pinfunction "4_4") (pintype "passive"))
    )
    (net (code "30") (name "/TX2") (class "Default")
      (node (ref "ESP1") (pin "28") (pinfunction "TX2/IO17_28") (pintype "bidirectional"))
      (node (ref "IC1") (pin "1") (pinfunction "RC7/RX/DT_1") (pintype "bidirectional"))
      (node (ref "UART_2") (pin "4") (pinfunction "4_4") (pintype "passive"))
    )
    (net (code "31") (name "/TXD0") (class "Default")
      (node (ref "ESP1") (pin "35") (pinfunction "TXD0_35") (pintype "bidirectional"))
      (node (ref "U3") (pin "3") (pinfunction "RXD_3") (pintype "input"))
    )
    (net (code "32") (name "/UD+") (class "Default")
      (node (ref "J1") (pin "A6") (pinfunction "DP1_A6") (pintype "bidirectional"))
      (node (ref "J1") (pin "B6") (pinfunction "DP2_B6") (pintype "bidirectional"))
      (node (ref "U3") (pin "5") (pinfunction "UD+_5") (pintype "bidirectional"))
    )
    (net (code "33") (name "/UD-") (class "Default")
      (node (ref "J1") (pin "A7") (pinfunction "DN1_A7") (pintype "bidirectional"))
      (node (ref "J1") (pin "B7") (pinfunction "DN2_B7") (pintype "bidirectional"))
      (node (ref "U3") (pin "6") (pinfunction "UD-_6") (pintype "bidirectional"))
    )
    (net (code "34") (name "/buszer") (class "Default")
      (node (ref "2SC1815") (pin "1") (pinfunction "B_1") (pintype "passive"))
      (node (ref "IC1") (pin "5") (pinfunction "RD7/PSP7_5") (pintype "bidirectional"))
      (node (ref "R36") (pin "1") (pinfunction "1_1") (pintype "passive"))
    )
    (net (code "35") (name "/rb6") (class "Default")
      (node (ref "IC1") (pin "16") (pinfunction "RB6/PGC_16") (pintype "bidirectional"))
      (node (ref "JP3") (pin "5") (pinfunction "5_5") (pintype "passive"))
    )
    (net (code "36") (name "/rb7") (class "Default")
      (node (ref "IC1") (pin "17") (pinfunction "RB7/PGD_17") (pintype "bidirectional"))
      (node (ref "JP3") (pin "4") (pinfunction "4_4") (pintype "passive"))
    )
    (net (code "37") (name "/reset") (class "Default")
      (node (ref "C1") (pin "2") (pinfunction "2_2") (pintype "passive"))
      (node (ref "IC1") (pin "18") (pinfunction "MCLR/VPP_18") (pintype "bidirectional"))
      (node (ref "JP3") (pin "1") (pinfunction "1_1") (pintype "passive"))
      (node (ref "R8") (pin "1") (pinfunction "1_1") (pintype "passive"))
      (node (ref "SW2") (pin "2") (pinfunction "2_2") (pintype "passive"))
    )
    (net (code "38") (name "/ta1") (class "Default")
      (node (ref "C9") (pin "2") (pinfunction "2_2") (pintype "passive"))
      (node (ref "IC1") (pin "30") (pinfunction "OSC1/CLKI_30") (pintype "bidirectional"))
      (node (ref "Y2") (pin "2") (pinfunction "2_2") (pintype "passive"))
    )
    (net (code "39") (name "/ta2") (class "Default")
      (node (ref "C11") (pin "2") (pinfunction "2_2") (pintype "passive"))
      (node (ref "IC1") (pin "31") (pinfunction "OSC2/CLKO_31") (pintype "bidirectional"))
      (node (ref "Y2") (pin "1") (pinfunction "1_1") (pintype "passive"))
    )
    (net (code "40") (name "A+24") (class "Default")
      (node (ref "D2") (pin "1") (pinfunction "1_1") (pintype "passive"))
      (node (ref "RUEF1") (pin "2") (pinfunction "2_2") (pintype "passive"))
      (node (ref "UU1") (pin "1") (pinfunction "IN+_1") (pintype "passive"))
    )
    (net (code "41") (name "GND") (class "Default")
      (node (ref "AMS1117") (pin "1") (pinfunction "GND_1") (pintype "passive"))
      (node (ref "BUZZER") (pin "2") (pinfunction "2_2") (pintype "passive"))
      (node (ref "C1") (pin "1") (pinfunction "1_1") (pintype "passive"))
      (node (ref "C11") (pin "1") (pinfunction "1_1") (pintype "passive"))
      (node (ref "C12") (pin "2") (pinfunction "2_2") (pintype "passive"))
      (node (ref "C13") (pin "1") (pinfunction "1_1") (pintype "passive"))
      (node (ref "C14") (pin "1") (pinfunction "1_1") (pintype "passive"))
      (node (ref "C7") (pin "2") (pinfunction "2_2") (pintype "passive"))
      (node (ref "C8") (pin "2") (pinfunction "2_2") (pintype "passive"))
      (node (ref "C9") (pin "1") (pinfunction "1_1") (pintype "passive"))
      (node (ref "CP3") (pin "2") (pinfunction "2_2") (pintype "passive"))
      (node (ref "CP4") (pin "2") (pinfunction "2_2") (pintype "passive"))
      (node (ref "CP5") (pin "2") (pinfunction "2_2") (pintype "passive"))
      (node (ref "CP6") (pin "2") (pinfunction "2_2") (pintype "passive"))
      (node (ref "D1") (pin "2") (pinfunction "2_2") (pintype "passive"))
      (node (ref "D3") (pin "A") (pinfunction "A_A") (pintype "passive"))
      (node (ref "D4") (pin "A") (pinfunction "A_A") (pintype "passive"))
      (node (ref "D5") (pin "A") (pinfunction "A_A") (pintype "passive"))
      (node (ref "ESP1") (pin "1") (pinfunction "GND_1") (pintype "power_in"))
      (node (ref "ESP1") (pin "15") (pinfunction "GND_15") (pintype "power_in"))
      (node (ref "ESP1") (pin "38") (pinfunction "GND_38") (pintype "power_in"))
      (node (ref "ESP1") (pin "39") (pinfunction "GND_39") (pintype "power_in"))
      (node (ref "FLAST1") (pin "1") (pinfunction "1_1") (pintype "passive"))
      (node (ref "IC1") (pin "29") (pinfunction "VSS_29") (pintype "bidirectional"))
      (node (ref "IC1") (pin "6") (pinfunction "VSS_6") (pintype "bidirectional"))
      (node (ref "J1") (pin "A1_B12") (pinfunction "GND_A1_B12") (pintype "power_in"))
      (node (ref "J1") (pin "B1_A12") (pinfunction "GND_B1_A12") (pintype "power_in"))
      (node (ref "J1") (pin "S1") (pinfunction "SHIELD_S1") (pintype "passive"))
      (node (ref "J1") (pin "S2") (pinfunction "SHIELD_S2") (pintype "passive"))
      (node (ref "JP3") (pin "3") (pinfunction "3_3") (pintype "passive"))
      (node (ref "LED2") (pin "2") (pinfunction "2_2") (pintype "passive"))
      (node (ref "LED3") (pin "2") (pinfunction "2_2") (pintype "passive"))
      (node (ref "LED9") (pin "2") (pinfunction "2_2") (pintype "passive"))
      (node (ref "OLED") (pin "2") (pinfunction "2_2") (pintype "passive"))
      (node (ref "OPPTO1") (pin "3") (pinfunction "E_3") (pintype "passive"))
      (node (ref "OPPTO2") (pin "3") (pinfunction "E_3") (pintype "passive"))
      (node (ref "OPPTO3") (pin "3") (pinfunction "E_3") (pintype "passive"))
      (node (ref "P1") (pin "8") (pinfunction "8_8") (pintype "passive"))
      (node (ref "PC1") (pin "2") (pinfunction "C_2") (pintype "passive"))
      (node (ref "PC2") (pin "2") (pinfunction "C_2") (pintype "passive"))
      (node (ref "PC3") (pin "2") (pinfunction "C_2") (pintype "passive"))
      (node (ref "R1") (pin "2") (pinfunction "2_2") (pintype "passive"))
      (node (ref "R11") (pin "2") (pinfunction "2_2") (pintype "passive"))
      (node (ref "R14") (pin "1") (pinfunction "1_1") (pintype "passive"))
      (node (ref "R16") (pin "1") (pinfunction "1_1") (pintype "passive"))
      (node (ref "R25") (pin "2") (pinfunction "2_2") (pintype "passive"))
      (node (ref "R28") (pin "1") (pinfunction "1_1") (pintype "passive"))
      (node (ref "R34") (pin "2") (pinfunction "2_2") (pintype "passive"))
      (node (ref "R5") (pin "1") (pinfunction "1_1") (pintype "passive"))
      (node (ref "REST1") (pin "1") (pinfunction "1_1") (pintype "passive"))
      (node (ref "RL1") (pin "1") (pinfunction "1_1") (pintype "bidirectional"))
      (node (ref "RL2") (pin "1") (pinfunction "1_1") (pintype "bidirectional"))
      (node (ref "RL3") (pin "1") (pinfunction "1_1") (pintype "bidirectional"))
      (node (ref "SW2") (pin "1") (pinfunction "1_1") (pintype "passive"))
      (node (ref "U3") (pin "1") (pinfunction "GND_1") (pintype "power_in"))
      (node (ref "UART_2") (pin "2") (pinfunction "2_2") (pintype "passive"))
      (node (ref "UU1") (pin "3") (pinfunction "OUT-_3") (pintype "passive"))
      (node (ref "VR2") (pin "3") (pinfunction "GROUND_3") (pintype "power_in"))
      (node (ref "VR2") (pin "5") (pinfunction "~{ON}/OFF_5") (pintype "input"))
      (node (ref "VR2") (pin "6") (pinfunction "GND_TAB_6") (pintype "power_in"))
    )
    (net (code "42") (name "GND_A") (class "Default")
      (node (ref "D2") (pin "2") (pinfunction "2_2") (pintype "passive"))
      (node (ref "JACK DC2") (pin "2") (pinfunction "TN_2") (pintype "passive"))
      (node (ref "P3") (pin "1") (pinfunction "1_1") (pintype "passive"))
      (node (ref "P3") (pin "2") (pinfunction "2_2") (pintype "passive"))
      (node (ref "UU1") (pin "2") (pinfunction "IN-_2") (pintype "passive"))
    )
    (net (code "43") (name "Net-(1-B)") (class "Default")
      (node (ref "1") (pin "1") (pinfunction "B_1") (pintype "passive"))
      (node (ref "R13") (pin "2") (pinfunction "2_2") (pintype "passive"))
      (node (ref "R14") (pin "2") (pinfunction "2_2") (pintype "passive"))
    )
    (net (code "44") (name "Net-(1-E)") (class "Default")
      (node (ref "1") (pin "3") (pinfunction "E_3") (pintype "passive"))
      (node (ref "D3") (pin "K") (pinfunction "K_K") (pintype "passive"))
      (node (ref "LED4") (pin "1") (pinfunction "1_1") (pintype "passive"))
      (node (ref "RL1") (pin "2") (pinfunction "2_2") (pintype "bidirectional"))
    )
    (net (code "45") (name "Net-(2-B)") (class "Default")
      (node (ref "2") (pin "1") (pinfunction "B_1") (pintype "passive"))
      (node (ref "R15") (pin "2") (pinfunction "2_2") (pintype "passive"))
      (node (ref "R16") (pin "2") (pinfunction "2_2") (pintype "passive"))
    )
    (net (code "46") (name "Net-(2-E)") (class "Default")
      (node (ref "2") (pin "3") (pinfunction "E_3") (pintype "passive"))
      (node (ref "D4") (pin "K") (pinfunction "K_K") (pintype "passive"))
      (node (ref "LED1") (pin "1") (pinfunction "1_1") (pintype "passive"))
      (node (ref "RL2") (pin "2") (pinfunction "2_2") (pintype "bidirectional"))
    )
    (net (code "47") (name "Net-(2SC1815-E)") (class "Default")
      (node (ref "2SC1815") (pin "3") (pinfunction "E_3") (pintype "passive"))
      (node (ref "BUZZER") (pin "1") (pinfunction "1_1") (pintype "passive"))
      (node (ref "R36") (pin "2") (pinfunction "2_2") (pintype "passive"))
    )
    (net (code "48") (name "Net-(3-B)") (class "Default")
      (node (ref "3") (pin "1") (pinfunction "B_1") (pintype "passive"))
      (node (ref "R27") (pin "2") (pinfunction "2_2") (pintype "passive"))
      (node (ref "R28") (pin "2") (pinfunction "2_2") (pintype "passive"))
    )
    (net (code "49") (name "Net-(3-E)") (class "Default")
      (node (ref "3") (pin "3") (pinfunction "E_3") (pintype "passive"))
      (node (ref "D5") (pin "K") (pinfunction "K_K") (pintype "passive"))
      (node (ref "LED7") (pin "1") (pinfunction "1_1") (pintype "passive"))
      (node (ref "RL3") (pin "2") (pinfunction "2_2") (pintype "bidirectional"))
    )
    (net (code "50") (name "Net-(J1-CC1)") (class "Default")
      (node (ref "J1") (pin "A5") (pinfunction "CC1_A5") (pintype "bidirectional"))
      (node (ref "R5") (pin "2") (pinfunction "2_2") (pintype "passive"))
    )
    (net (code "51") (name "Net-(LED1-Pad2)") (class "Default")
      (node (ref "LED1") (pin "2") (pinfunction "2_2") (pintype "passive"))
      (node (ref "R1") (pin "1") (pinfunction "1_1") (pintype "passive"))
    )
    (net (code "52") (name "Net-(LED2-Pad1)") (class "Default")
      (node (ref "LED2") (pin "1") (pinfunction "1_1") (pintype "passive"))
      (node (ref "R3") (pin "1") (pinfunction "1_1") (pintype "passive"))
    )
    (net (code "53") (name "Net-(LED3-Pad1)") (class "Default")
      (node (ref "LED3") (pin "1") (pinfunction "1_1") (pintype "passive"))
      (node (ref "R4") (pin "1") (pinfunction "1_1") (pintype "passive"))
    )
    (net (code "54") (name "Net-(LED4-Pad2)") (class "Default")
      (node (ref "LED4") (pin "2") (pinfunction "2_2") (pintype "passive"))
      (node (ref "R11") (pin "1") (pinfunction "1_1") (pintype "passive"))
    )
    (net (code "55") (name "Net-(LED7-Pad2)") (class "Default")
      (node (ref "LED7") (pin "2") (pinfunction "2_2") (pintype "passive"))
      (node (ref "R25") (pin "1") (pinfunction "1_1") (pintype "passive"))
    )
    (net (code "56") (name "Net-(LED9-Pad1)") (class "Default")
      (node (ref "LED9") (pin "1") (pinfunction "1_1") (pintype "passive"))
      (node (ref "R35") (pin "2") (pinfunction "2_2") (pintype "passive"))
    )
    (net (code "57") (name "Net-(Led5-B-Pad2)") (class "Default")
      (node (ref "Led5") (pin "2") (pinfunction "B_2") (pintype "passive"))
      (node (ref "R18") (pin "1") (pinfunction "1_1") (pintype "passive"))
    )
    (net (code "58") (name "Net-(Led6-B-Pad2)") (class "Default")
      (node (ref "Led6") (pin "2") (pinfunction "B_2") (pintype "passive"))
      (node (ref "R22") (pin "1") (pinfunction "1_1") (pintype "passive"))
    )
    (net (code "59") (name "Net-(Led8-B-Pad2)") (class "Default")
      (node (ref "Led8") (pin "2") (pinfunction "B_2") (pintype "passive"))
      (node (ref "R30") (pin "1") (pinfunction "1_1") (pintype "passive"))
    )
    (net (code "60") (name "Net-(OPPTO1-C)") (class "Default")
      (node (ref "OPPTO1") (pin "2") (pinfunction "C_2") (pintype "passive"))
      (node (ref "R19") (pin "2") (pinfunction "2_2") (pintype "passive"))
      (node (ref "R20") (pin "2") (pinfunction "2_2") (pintype "passive"))
    )
    (net (code "61") (name "Net-(OPPTO2-C)") (class "Default")
      (node (ref "OPPTO2") (pin "2") (pinfunction "C_2") (pintype "passive"))
      (node (ref "R23") (pin "2") (pinfunction "2_2") (pintype "passive"))
      (node (ref "R24") (pin "2") (pinfunction "2_2") (pintype "passive"))
    )
    (net (code "62") (name "Net-(OPPTO3-C)") (class "Default")
      (node (ref "OPPTO3") (pin "2") (pinfunction "C_2") (pintype "passive"))
      (node (ref "R31") (pin "2") (pinfunction "2_2") (pintype "passive"))
      (node (ref "R32") (pin "2") (pinfunction "2_2") (pintype "passive"))
    )
    (net (code "63") (name "Net-(PC1-A)") (class "Default")
      (node (ref "PC1") (pin "1") (pinfunction "A_1") (pintype "passive"))
      (node (ref "R12") (pin "1") (pinfunction "1_1") (pintype "passive"))
    )
    (net (code "64") (name "Net-(PC1-E)") (class "Default")
      (node (ref "PC1") (pin "3") (pinfunction "E_3") (pintype "passive"))
      (node (ref "R13") (pin "1") (pinfunction "1_1") (pintype "passive"))
    )
    (net (code "65") (name "Net-(PC2-A)") (class "Default")
      (node (ref "PC2") (pin "1") (pinfunction "A_1") (pintype "passive"))
      (node (ref "R2") (pin "1") (pinfunction "1_1") (pintype "passive"))
    )
    (net (code "66") (name "Net-(PC2-E)") (class "Default")
      (node (ref "PC2") (pin "3") (pinfunction "E_3") (pintype "passive"))
      (node (ref "R15") (pin "1") (pinfunction "1_1") (pintype "passive"))
    )
    (net (code "67") (name "Net-(PC3-A)") (class "Default")
      (node (ref "PC3") (pin "1") (pinfunction "A_1") (pintype "passive"))
      (node (ref "R26") (pin "1") (pinfunction "1_1") (pintype "passive"))
    )
    (net (code "68") (name "Net-(PC3-E)") (class "Default")
      (node (ref "PC3") (pin "3") (pinfunction "E_3") (pintype "passive"))
      (node (ref "R27") (pin "1") (pinfunction "1_1") (pintype "passive"))
    )
    (net (code "69") (name "Net-(Q1-B)") (class "Default")
      (node (ref "Q1") (pin "1") (pinfunction "B_1") (pintype "passive"))
      (node (ref "R6") (pin "2") (pinfunction "2_2") (pintype "passive"))
    )
    (net (code "70") (name "Net-(Q2-B)") (class "Default")
      (node (ref "Q2") (pin "1") (pinfunction "B_1") (pintype "passive"))
      (node (ref "R7") (pin "1") (pinfunction "1_1") (pintype "passive"))
    )
    (net (code "71") (name "Net-(VR2-OUTPUT)") (class "Default")
      (node (ref "D1") (pin "1") (pinfunction "1_1") (pintype "passive"))
      (node (ref "L2") (pin "1") (pinfunction "1_1") (pintype "passive"))
      (node (ref "VR2") (pin "2") (pinfunction "OUTPUT_2") (pintype "output"))
    )
    (net (code "72") (name "VCC") (class "Default")
      (node (ref "C7") (pin "1") (pinfunction "1_1") (pintype "passive"))
      (node (ref "CP3") (pin "1") (pinfunction "1_1") (pintype "passive"))
      (node (ref "CP4") (pin "1") (pinfunction "1_1") (pintype "passive"))
      (node (ref "UU1") (pin "4") (pinfunction "OUT+_4") (pintype "passive"))
      (node (ref "VR2") (pin "1") (pinfunction "VIN_1") (pintype "input"))
    )
    (net (code "73") (name "VDD_3.3V") (class "Default")
      (node (ref "AMS1117") (pin "2") (pinfunction "OUT_2") (pintype "passive"))
      (node (ref "AMS1117") (pin "4") (pinfunction "OUT_4") (pintype "passive"))
      (node (ref "C12") (pin "1") (pinfunction "1_1") (pintype "passive"))
      (node (ref "CP6") (pin "1") (pinfunction "1_1") (pintype "passive"))
      (node (ref "ESP1") (pin "2") (pinfunction "3V3_2") (pintype "power_in"))
      (node (ref "OLED") (pin "1") (pinfunction "1_1") (pintype "passive"))
      (node (ref "P1") (pin "6") (pinfunction "6_6") (pintype "passive"))
      (node (ref "R10") (pin "2") (pinfunction "2_2") (pintype "passive"))
      (node (ref "R3") (pin "2") (pinfunction "2_2") (pintype "passive"))
      (node (ref "R9") (pin "2") (pinfunction "2_2") (pintype "passive"))
    )
    (net (code "74") (name "unconnected-(ESP1-CLK-Pad20)") (class "Default")
      (node (ref "ESP1") (pin "20") (pinfunction "CLK_20") (pintype "bidirectional"))
    )
    (net (code "75") (name "unconnected-(ESP1-CMD-Pad19)") (class "Default")
      (node (ref "ESP1") (pin "19") (pinfunction "CMD_19") (pintype "bidirectional"))
    )
    (net (code "76") (name "unconnected-(ESP1-IO2-Pad24)") (class "Default")
      (node (ref "ESP1") (pin "24") (pinfunction "IO2_24") (pintype "bidirectional"))
    )
    (net (code "77") (name "unconnected-(ESP1-IO4-Pad26)") (class "Default")
      (node (ref "ESP1") (pin "26") (pinfunction "IO4_26") (pintype "bidirectional"))
    )
    (net (code "78") (name "unconnected-(ESP1-IO12{slash}HSPI_MISO-Pad14)") (class "Default")
      (node (ref "ESP1") (pin "14") (pinfunction "IO12/HSPI_MISO_14") (pintype "bidirectional"))
    )
    (net (code "79") (name "unconnected-(ESP1-IO13{slash}HSPI_MOSI-Pad16)") (class "Default")
      (node (ref "ESP1") (pin "16") (pinfunction "IO13/HSPI_MOSI_16") (pintype "bidirectional"))
    )
    (net (code "80") (name "unconnected-(ESP1-IO14{slash}HSPICLK-Pad13)") (class "Default")
      (node (ref "ESP1") (pin "13") (pinfunction "IO14/HSPICLK_13") (pintype "bidirectional"))
    )
    (net (code "81") (name "unconnected-(ESP1-IO15-Pad23)") (class "Default")
      (node (ref "ESP1") (pin "23") (pinfunction "IO15_23") (pintype "bidirectional"))
    )
    (net (code "82") (name "unconnected-(ESP1-IO25-Pad10)") (class "Default")
      (node (ref "ESP1") (pin "10") (pinfunction "IO25_10") (pintype "bidirectional"))
    )
    (net (code "83") (name "unconnected-(ESP1-IO26-Pad11)") (class "Default")
      (node (ref "ESP1") (pin "11") (pinfunction "IO26_11") (pintype "bidirectional"))
    )
    (net (code "84") (name "unconnected-(ESP1-IO27-Pad12)") (class "Default")
      (node (ref "ESP1") (pin "12") (pinfunction "IO27_12") (pintype "bidirectional"))
    )
    (net (code "85") (name "unconnected-(ESP1-IO32-Pad8)") (class "Default")
      (node (ref "ESP1") (pin "8") (pinfunction "IO32_8") (pintype "bidirectional"))
    )
    (net (code "86") (name "unconnected-(ESP1-IO33-Pad9)") (class "Default")
      (node (ref "ESP1") (pin "9") (pinfunction "IO33_9") (pintype "bidirectional"))
    )
    (net (code "87") (name "unconnected-(ESP1-IO34-Pad6)") (class "Default")
      (node (ref "ESP1") (pin "6") (pinfunction "IO34_6") (pintype "input"))
    )
    (net (code "88") (name "unconnected-(ESP1-IO35-Pad7)") (class "Default")
      (node (ref "ESP1") (pin "7") (pinfunction "IO35_7") (pintype "input"))
    )
    (net (code "89") (name "unconnected-(ESP1-NC-Pad32)") (class "Default")
      (node (ref "ESP1") (pin "32") (pinfunction "NC_32") (pintype "passive"))
    )
    (net (code "90") (name "unconnected-(ESP1-SD0-Pad21)") (class "Default")
      (node (ref "ESP1") (pin "21") (pinfunction "SD0_21") (pintype "bidirectional"))
    )
    (net (code "91") (name "unconnected-(ESP1-SD1-Pad22)") (class "Default")
      (node (ref "ESP1") (pin "22") (pinfunction "SD1_22") (pintype "bidirectional"))
    )
    (net (code "92") (name "unconnected-(ESP1-SD2{slash}RX1-Pad17)") (class "Default")
      (node (ref "ESP1") (pin "17") (pinfunction "SD2/RX1_17") (pintype "bidirectional"))
    )
    (net (code "93") (name "unconnected-(ESP1-SD3{slash}TX1-Pad18)") (class "Default")
      (node (ref "ESP1") (pin "18") (pinfunction "SD3/TX1_18") (pintype "bidirectional"))
    )
    (net (code "94") (name "unconnected-(ESP1-SENSOR_VN{slash}IO39-Pad5)") (class "Default")
      (node (ref "ESP1") (pin "5") (pinfunction "SENSOR_VN/IO39_5") (pintype "input"))
    )
    (net (code "95") (name "unconnected-(ESP1-SENSOR_VP{slash}IO36-Pad4)") (class "Default")
      (node (ref "ESP1") (pin "4") (pinfunction "SENSOR_VP/IO36_4") (pintype "input"))
    )
    (net (code "96") (name "unconnected-(ESP1-VSPI_CLK{slash}IO18-Pad30)") (class "Default")
      (node (ref "ESP1") (pin "30") (pinfunction "VSPI_CLK/IO18_30") (pintype "bidirectional"))
    )
    (net (code "97") (name "unconnected-(ESP1-VSPI_CS0{slash}IO5-Pad29)") (class "Default")
      (node (ref "ESP1") (pin "29") (pinfunction "VSPI_CS0/IO5_29") (pintype "bidirectional"))
    )
    (net (code "98") (name "unconnected-(ESP1-VSPI_MISO{slash}IO19-Pad31)") (class "Default")
      (node (ref "ESP1") (pin "31") (pinfunction "VSPI_MISO/IO19_31") (pintype "bidirectional"))
    )
    (net (code "99") (name "unconnected-(ESP1-VSPI_MOSI{slash}IO23-Pad37)") (class "Default")
      (node (ref "ESP1") (pin "37") (pinfunction "VSPI_MOSI/IO23_37") (pintype "bidirectional"))
    )
    (net (code "100") (name "unconnected-(IC1-NC-Pad12)") (class "Default")
      (node (ref "IC1") (pin "12") (pinfunction "NC_12") (pintype "bidirectional"))
    )
    (net (code "101") (name "unconnected-(IC1-NC-Pad13)") (class "Default")
      (node (ref "IC1") (pin "13") (pinfunction "NC_13") (pintype "bidirectional"))
    )
    (net (code "102") (name "unconnected-(IC1-NC-Pad33)") (class "Default")
      (node (ref "IC1") (pin "33") (pinfunction "NC_33") (pintype "bidirectional"))
    )
    (net (code "103") (name "unconnected-(IC1-NC-Pad34)") (class "Default")
      (node (ref "IC1") (pin "34") (pinfunction "NC_34") (pintype "bidirectional"))
    )
    (net (code "104") (name "unconnected-(IC1-RA1{slash}AN1-Pad20)") (class "Default")
      (node (ref "IC1") (pin "20") (pinfunction "RA1/AN1_20") (pintype "bidirectional"))
    )
    (net (code "105") (name "unconnected-(IC1-RA2{slash}AN2{slash}VREF-{slash}CVREF-Pad21)") (class "Default")
      (node (ref "IC1") (pin "21") (pinfunction "RA2/AN2/VREF-/CVREF_21") (pintype "bidirectional"))
    )
    (net (code "106") (name "unconnected-(IC1-RA3{slash}AN3{slash}VREF+-Pad22)") (class "Default")
      (node (ref "IC1") (pin "22") (pinfunction "RA3/AN3/VREF+_22") (pintype "bidirectional"))
    )
    (net (code "107") (name "unconnected-(IC1-RA4{slash}T0CKI{slash}C1OUT-Pad23)") (class "Default")
      (node (ref "IC1") (pin "23") (pinfunction "RA4/T0CKI/C1OUT_23") (pintype "bidirectional"))
    )
    (net (code "108") (name "unconnected-(IC1-RA5{slash}AN4{slash}SS{slash}C2OUT-Pad24)") (class "Default")
      (node (ref "IC1") (pin "24") (pinfunction "RA5/AN4/SS/C2OUT_24") (pintype "bidirectional"))
    )
    (net (code "109") (name "unconnected-(IC1-RB0{slash}INT-Pad8)") (class "Default")
      (node (ref "IC1") (pin "8") (pinfunction "RB0/INT_8") (pintype "bidirectional"))
    )
    (net (code "110") (name "unconnected-(IC1-RB1-Pad9)") (class "Default")
      (node (ref "IC1") (pin "9") (pinfunction "RB1_9") (pintype "bidirectional"))
    )
    (net (code "111") (name "unconnected-(IC1-RB2-Pad10)") (class "Default")
      (node (ref "IC1") (pin "10") (pinfunction "RB2_10") (pintype "bidirectional"))
    )
    (net (code "112") (name "unconnected-(IC1-RB3{slash}PGM-Pad11)") (class "Default")
      (node (ref "IC1") (pin "11") (pinfunction "RB3/PGM_11") (pintype "bidirectional"))
    )
    (net (code "113") (name "unconnected-(IC1-RB4-Pad14)") (class "Default")
      (node (ref "IC1") (pin "14") (pinfunction "RB4_14") (pintype "bidirectional"))
    )
    (net (code "114") (name "unconnected-(IC1-RB5-Pad15)") (class "Default")
      (node (ref "IC1") (pin "15") (pinfunction "RB5_15") (pintype "bidirectional"))
    )
    (net (code "115") (name "unconnected-(IC1-RC0{slash}T1OSO{slash}T1CKI-Pad32)") (class "Default")
      (node (ref "IC1") (pin "32") (pinfunction "RC0/T1OSO/T1CKI_32") (pintype "bidirectional"))
    )
    (net (code "116") (name "unconnected-(IC1-RC1{slash}T1OSI{slash}CCP2-Pad35)") (class "Default")
      (node (ref "IC1") (pin "35") (pinfunction "RC1/T1OSI/CCP2_35") (pintype "bidirectional"))
    )
    (net (code "117") (name "unconnected-(IC1-RC3{slash}SCK{slash}SCL-Pad37)") (class "Default")
      (node (ref "IC1") (pin "37") (pinfunction "RC3/SCK/SCL_37") (pintype "bidirectional"))
    )
    (net (code "118") (name "unconnected-(IC1-RC4{slash}SDI{slash}SDA-Pad42)") (class "Default")
      (node (ref "IC1") (pin "42") (pinfunction "RC4/SDI/SDA_42") (pintype "bidirectional"))
    )
    (net (code "119") (name "unconnected-(IC1-RC5{slash}SDO-Pad43)") (class "Default")
      (node (ref "IC1") (pin "43") (pinfunction "RC5/SDO_43") (pintype "bidirectional"))
    )
    (net (code "120") (name "unconnected-(IC1-RE0{slash}RD{slash}AN5-Pad25)") (class "Default")
      (node (ref "IC1") (pin "25") (pinfunction "RE0/RD/AN5_25") (pintype "bidirectional"))
    )
    (net (code "121") (name "unconnected-(IC1-RE1{slash}WR{slash}AN6-Pad26)") (class "Default")
      (node (ref "IC1") (pin "26") (pinfunction "RE1/WR/AN6_26") (pintype "bidirectional"))
    )
    (net (code "122") (name "unconnected-(IC1-RE2{slash}CS{slash}AN7-Pad27)") (class "Default")
      (node (ref "IC1") (pin "27") (pinfunction "RE2/CS/AN7_27") (pintype "bidirectional"))
    )
    (net (code "123") (name "unconnected-(IPEX-GND-Pad2)") (class "Default")
      (node (ref "IPEX") (pin "2") (pinfunction "GND_2") (pintype "passive"))
    )
    (net (code "124") (name "unconnected-(IPEX-GND-Pad3)") (class "Default")
      (node (ref "IPEX") (pin "3") (pinfunction "GND_3") (pintype "passive"))
    )
    (net (code "125") (name "unconnected-(IPEX-GND-Pad4)") (class "Default")
      (node (ref "IPEX") (pin "4") (pinfunction "GND_4") (pintype "passive"))
    )
    (net (code "126") (name "unconnected-(IPEX-GND-Pad5)") (class "Default")
      (node (ref "IPEX") (pin "5") (pinfunction "GND_5") (pintype "passive"))
    )
    (net (code "127") (name "unconnected-(J1-CC2-PadB5)") (class "Default")
      (node (ref "J1") (pin "B5") (pinfunction "CC2_B5") (pintype "bidirectional"))
    )
    (net (code "128") (name "unconnected-(J1-SBU1-PadA8)") (class "Default")
      (node (ref "J1") (pin "A8") (pinfunction "SBU1_A8") (pintype "bidirectional"))
    )
    (net (code "129") (name "unconnected-(J1-SBU2-PadB8)") (class "Default")
      (node (ref "J1") (pin "B8") (pinfunction "SBU2_B8") (pintype "bidirectional"))
    )
    (net (code "130") (name "unconnected-(J1-SHIELD-PadS3)") (class "Default")
      (node (ref "J1") (pin "S3") (pinfunction "SHIELD_S3") (pintype "passive"))
    )
    (net (code "131") (name "unconnected-(J1-SHIELD-PadS4)") (class "Default")
      (node (ref "J1") (pin "S4") (pinfunction "SHIELD_S4") (pintype "passive"))
    )
    (net (code "132") (name "unconnected-(JACK DC2-S-Pad3)") (class "Default")
      (node (ref "JACK DC2") (pin "3") (pinfunction "S_3") (pintype "power_in"))
    )
    (net (code "133") (name "unconnected-(JP3-Pad6)") (class "Default")
      (node (ref "JP3") (pin "6") (pinfunction "6_6") (pintype "passive"))
    )
    (net (code "134") (name "unconnected-(U3-NC.-Pad7)") (class "Default")
      (node (ref "U3") (pin "7") (pinfunction "NC._7") (pintype "passive"))
    )
    (net (code "135") (name "unconnected-(U3-R232-Pad15)") (class "Default")
      (node (ref "U3") (pin "15") (pinfunction "R232_15") (pintype "input"))
    )
    (net (code "136") (name "unconnected-(U3-~{CTS}-Pad9)") (class "Default")
      (node (ref "U3") (pin "9") (pinfunction "~{CTS}_9") (pintype "input"))
    )
    (net (code "137") (name "unconnected-(U3-~{DCD}-Pad12)") (class "Default")
      (node (ref "U3") (pin "12") (pinfunction "~{DCD}_12") (pintype "input"))
    )
    (net (code "138") (name "unconnected-(U3-~{DSR}-Pad10)") (class "Default")
      (node (ref "U3") (pin "10") (pinfunction "~{DSR}_10") (pintype "input"))
    )
    (net (code "139") (name "unconnected-(U3-~{OUT}-Pad8)") (class "Default")
      (node (ref "U3") (pin "8") (pinfunction "~{OUT}_8") (pintype "output"))
    )
    (net (code "140") (name "unconnected-(U3-~{RI}-Pad11)") (class "Default")
      (node (ref "U3") (pin "11") (pinfunction "~{RI}_11") (pintype "input"))
    )
  )
)
